# RT1064_CoreBoard.net
KiCad netlist of a schematic drawn in Altium Designer
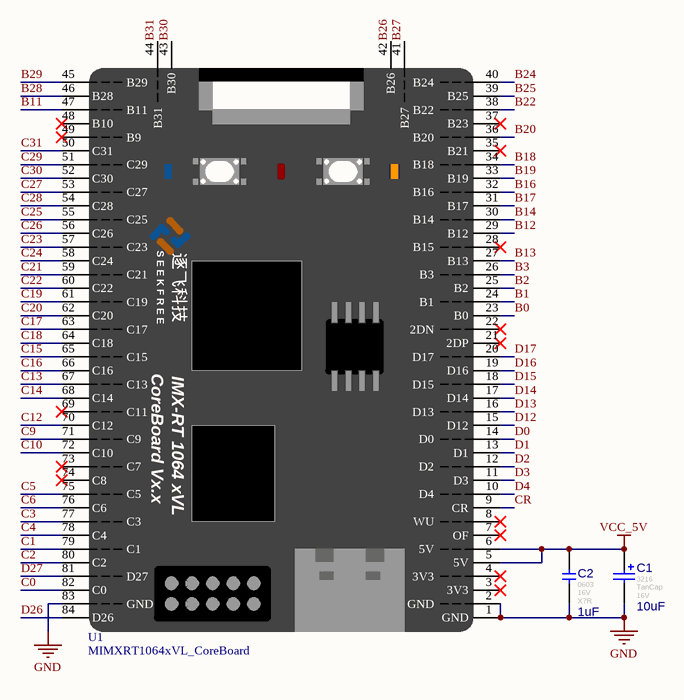
[diagram p0: RT1064_CoreBoard.SchDoc]

(export (version "E")
  (design (tool "Eeschema 10.0.6"))
  (components
    (comp (ref "C1")
      (value "10uF")
      (footprint "3216")
      (description "贴片钽电容 10uF 3216 16V")
      (fields
        (field (name "TYPE") "TanCap")
        (field (name "VOLTAGE") "16V")
        (field (name "Comment") "T-S 10uF 3216 16V")
      )
      (libsource (lib "RT1064 主板 V3.0 器件封装集成库") (part "T-S 10uF 3216 16V"))
    )
    (comp (ref "C2")
      (value "1uF")
      (footprint "0603")
      (description "贴片瓷片电容; MLCC; 0603(1608);")
      (fields
        (field (name "VOLTAGE") "16V")
        (field (name "TYPE") "X7R")
        (field (name "Comment") "1uF 16V X7R")
      )
      (libsource (lib "RT1064 主板 V3.0 器件封装集成库") (part "1uF 0603 16V X7R"))
    )
    (comp (ref "U1")
      (value "MIMXRT1064xVL_CoreBoard")
      (footprint "MIMXRT1064xVL_CoreBoard - 3D")
      (description "逐飞科技i.MX RT1064核心板整体原理，可直接使用")
      (libsource (lib "RT1064 V1.2核心板原理库") (part "MIMXRT1064xVL_CoreBoard"))
    )
  )
  (nets
    (net (code "1") (name "/B0") (class "Default")
      (node (ref "U1") (pin "23") (pinfunction "B0_23") (pintype "passive"))
    )
    (net (code "2") (name "/B1") (class "Default")
      (node (ref "U1") (pin "24") (pinfunction "B1_24") (pintype "passive"))
    )
    (net (code "3") (name "/B2") (class "Default")
      (node (ref "U1") (pin "25") (pinfunction "B2_25") (pintype "passive"))
    )
    (net (code "4") (name "/B3") (class "Default")
      (node (ref "U1") (pin "26") (pinfunction "B3_26") (pintype "passive"))
    )
    (net (code "5") (name "/B11") (class "Default")
      (node (ref "U1") (pin "47") (pinfunction "B11_47") (pintype "passive"))
    )
    (net (code "6") (name "/B12") (class "Default")
      (node (ref "U1") (pin "29") (pinfunction "B12_29") (pintype "passive"))
    )
    (net (code "7") (name "/B13") (class "Default")
      (node (ref "U1") (pin "27") (pinfunction "B13_27") (pintype "passive"))
    )
    (net (code "8") (name "/B14") (class "Default")
      (node (ref "U1") (pin "30") (pinfunction "B14_30") (pintype "passive"))
    )
    (net (code "9") (name "/B16") (class "Default")
      (node (ref "U1") (pin "32") (pinfunction "B16_32") (pintype "passive"))
    )
    (net (code "10") (name "/B17") (class "Default")
      (node (ref "U1") (pin "31") (pinfunction "B17_31") (pintype "passive"))
    )
    (net (code "11") (name "/B18") (class "Default")
      (node (ref "U1") (pin "34") (pinfunction "B18_34") (pintype "passive"))
    )
    (net (code "12") (name "/B19") (class "Default")
      (node (ref "U1") (pin "33") (pinfunction "B19_33") (pintype "passive"))
    )
    (net (code "13") (name "/B20") (class "Default")
      (node (ref "U1") (pin "36") (pinfunction "B20_36") (pintype "passive"))
    )
    (net (code "14") (name "/B22") (class "Default")
      (node (ref "U1") (pin "38") (pinfunction "B22_38") (pintype "passive"))
    )
    (net (code "15") (name "/B24") (class "Default")
      (node (ref "U1") (pin "40") (pinfunction "B24_40") (pintype "passive"))
    )
    (net (code "16") (name "/B25") (class "Default")
      (node (ref "U1") (pin "39") (pinfunction "B25_39") (pintype "passive"))
    )
    (net (code "17") (name "/B26") (class "Default")
      (node (ref "U1") (pin "42") (pinfunction "B26_42") (pintype "passive"))
    )
    (net (code "18") (name "/B27") (class "Default")
      (node (ref "U1") (pin "41") (pinfunction "B27_41") (pintype "passive"))
    )
    (net (code "19") (name "/B28") (class "Default")
      (node (ref "U1") (pin "46") (pinfunction "B28_46") (pintype "passive"))
    )
    (net (code "20") (name "/B29") (class "Default")
      (node (ref "U1") (pin "45") (pinfunction "B29_45") (pintype "passive"))
    )
    (net (code "21") (name "/B30") (class "Default")
      (node (ref "U1") (pin "43") (pinfunction "B30_43") (pintype "passive"))
    )
    (net (code "22") (name "/B31") (class "Default")
      (node (ref "U1") (pin "44") (pinfunction "B31_44") (pintype "passive"))
    )
    (net (code "23") (name "/C0") (class "Default")
      (node (ref "U1") (pin "82") (pinfunction "C0_82") (pintype "passive"))
    )
    (net (code "24") (name "/C1") (class "Default")
      (node (ref "U1") (pin "79") (pinfunction "C1_79") (pintype "passive"))
    )
    (net (code "25") (name "/C2") (class "Default")
      (node (ref "U1") (pin "80") (pinfunction "C2_80") (pintype "passive"))
    )
    (net (code "26") (name "/C3") (class "Default")
      (node (ref "U1") (pin "77") (pinfunction "C3_77") (pintype "passive"))
    )
    (net (code "27") (name "/C4") (class "Default")
      (node (ref "U1") (pin "78") (pinfunction "C4_78") (pintype "passive"))
    )
    (net (code "28") (name "/C5") (class "Default")
      (node (ref "U1") (pin "75") (pinfunction "C5_75") (pintype "passive"))
    )
    (net (code "29") (name "/C6") (class "Default")
      (node (ref "U1") (pin "76") (pinfunction "C6_76") (pintype "passive"))
    )
    (net (code "30") (name "/C9") (class "Default")
      (node (ref "U1") (pin "71") (pinfunction "C9_71") (pintype "passive"))
    )
    (net (code "31") (name "/C10") (class "Default")
      (node (ref "U1") (pin "72") (pinfunction "C10_72") (pintype "passive"))
    )
    (net (code "32") (name "/C12") (class "Default")
      (node (ref "U1") (pin "70") (pinfunction "C12_70") (pintype "passive"))
    )
    (net (code "33") (name "/C13") (class "Default")
      (node (ref "U1") (pin "67") (pinfunction "C13_67") (pintype "passive"))
    )
    (net (code "34") (name "/C14") (class "Default")
      (node (ref "U1") (pin "68") (pinfunction "C14_68") (pintype "passive"))
    )
    (net (code "35") (name "/C15") (class "Default")
      (node (ref "U1") (pin "65") (pinfunction "C15_65") (pintype "passive"))
    )
    (net (code "36") (name "/C16") (class "Default")
      (node (ref "U1") (pin "66") (pinfunction "C16_66") (pintype "passive"))
    )
    (net (code "37") (name "/C17") (class "Default")
      (node (ref "U1") (pin "63") (pinfunction "C17_63") (pintype "passive"))
    )
    (net (code "38") (name "/C18") (class "Default")
      (node (ref "U1") (pin "64") (pinfunction "C18_64") (pintype "passive"))
    )
    (net (code "39") (name "/C19") (class "Default")
      (node (ref "U1") (pin "61") (pinfunction "C19_61") (pintype "passive"))
    )
    (net (code "40") (name "/C20") (class "Default")
      (node (ref "U1") (pin "62") (pinfunction "C20_62") (pintype "passive"))
    )
    (net (code "41") (name "/C21") (class "Default")
      (node (ref "U1") (pin "59") (pinfunction "C21_59") (pintype "passive"))
    )
    (net (code "42") (name "/C22") (class "Default")
      (node (ref "U1") (pin "60") (pinfunction "C22_60") (pintype "passive"))
    )
    (net (code "43") (name "/C23") (class "Default")
      (node (ref "U1") (pin "57") (pinfunction "C23_57") (pintype "passive"))
    )
    (net (code "44") (name "/C24") (class "Default")
      (node (ref "U1") (pin "58") (pinfunction "C24_58") (pintype "passive"))
    )
    (net (code "45") (name "/C25") (class "Default")
      (node (ref "U1") (pin "55") (pinfunction "C25_55") (pintype "passive"))
    )
    (net (code "46") (name "/C26") (class "Default")
      (node (ref "U1") (pin "56") (pinfunction "C26_56") (pintype "passive"))
    )
    (net (code "47") (name "/C27") (class "Default")
      (node (ref "U1") (pin "53") (pinfunction "C27_53") (pintype "passive"))
    )
    (net (code "48") (name "/C28") (class "Default")
      (node (ref "U1") (pin "54") (pinfunction "C28_54") (pintype "passive"))
    )
    (net (code "49") (name "/C29") (class "Default")
      (node (ref "U1") (pin "51") (pinfunction "C29_51") (pintype "passive"))
    )
    (net (code "50") (name "/C30") (class "Default")
      (node (ref "U1") (pin "52") (pinfunction "C30_52") (pintype "passive"))
    )
    (net (code "51") (name "/C31") (class "Default")
      (node (ref "U1") (pin "50") (pinfunction "C31_50") (pintype "passive"))
    )
    (net (code "52") (name "/CR") (class "Default")
      (node (ref "U1") (pin "9") (pinfunction "CR_9") (pintype "passive"))
    )
    (net (code "53") (name "/D0") (class "Default")
      (node (ref "U1") (pin "14") (pinfunction "D0_14") (pintype "passive"))
    )
    (net (code "54") (name "/D1") (class "Default")
      (node (ref "U1") (pin "13") (pinfunction "D1_13") (pintype "passive"))
    )
    (net (code "55") (name "/D2") (class "Default")
      (node (ref "U1") (pin "12") (pinfunction "D2_12") (pintype "passive"))
    )
    (net (code "56") (name "/D3") (class "Default")
      (node (ref "U1") (pin "11") (pinfunction "D3_11") (pintype "passive"))
    )
    (net (code "57") (name "/D4") (class "Default")
      (node (ref "U1") (pin "10") (pinfunction "D4_10") (pintype "passive"))
    )
    (net (code "58") (name "/D12") (class "Default")
      (node (ref "U1") (pin "15") (pinfunction "D12_15") (pintype "passive"))
    )
    (net (code "59") (name "/D13") (class "Default")
      (node (ref "U1") (pin "16") (pinfunction "D13_16") (pintype "passive"))
    )
    (net (code "60") (name "/D14") (class "Default")
      (node (ref "U1") (pin "17") (pinfunction "D14_17") (pintype "passive"))
    )
    (net (code "61") (name "/D15") (class "Default")
      (node (ref "U1") (pin "18") (pinfunction "D15_18") (pintype "passive"))
    )
    (net (code "62") (name "/D16") (class "Default")
      (node (ref "U1") (pin "19") (pinfunction "D16_19") (pintype "passive"))
    )
    (net (code "63") (name "/D17") (class "Default")
      (node (ref "U1") (pin "20") (pinfunction "D17_20") (pintype "passive"))
    )
    (net (code "64") (name "/D26") (class "Default")
      (node (ref "U1") (pin "84") (pinfunction "D26_84") (pintype "passive"))
    )
    (net (code "65") (name "/D27") (class "Default")
      (node (ref "U1") (pin "81") (pinfunction "D27_81") (pintype "passive"))
    )
    (net (code "66") (name "GND") (class "Default")
      (node (ref "C1") (pin "2") (pinfunction "2_2") (pintype "passive"))
      (node (ref "C2") (pin "1") (pinfunction "1_1") (pintype "passive"))
      (node (ref "U1") (pin "1") (pinfunction "GND_1") (pintype "passive"))
      (node (ref "U1") (pin "2") (pinfunction "GND_2") (pintype "passive"))
      (node (ref "U1") (pin "83") (pinfunction "GND_83") (pintype "passive"))
    )
    (net (code "67") (name "VCC_5V") (class "Default")
      (node (ref "C1") (pin "1") (pinfunction "1_1") (pintype "passive"))
      (node (ref "C2") (pin "2") (pinfunction "2_2") (pintype "passive"))
      (node (ref "U1") (pin "5") (pinfunction "5V_5") (pintype "passive"))
      (node (ref "U1") (pin "6") (pinfunction "5V_6") (pintype "passive"))
    )
    (net (code "68") (name "unconnected-(U1-2DN-Pad22)") (class "Default")
      (node (ref "U1") (pin "22") (pinfunction "2DN_22") (pintype "passive+no_connect"))
    )
    (net (code "69") (name "unconnected-(U1-2DP-Pad21)") (class "Default")
      (node (ref "U1") (pin "21") (pinfunction "2DP_21") (pintype "passive+no_connect"))
    )
    (net (code "70") (name "unconnected-(U1-3V3-Pad3)") (class "Default")
      (node (ref "U1") (pin "3") (pinfunction "3V3_3") (pintype "passive+no_connect"))
    )
    (net (code "71") (name "unconnected-(U1-3V3-Pad4)") (class "Default")
      (node (ref "U1") (pin "4") (pinfunction "3V3_4") (pintype "passive+no_connect"))
    )
    (net (code "72") (name "unconnected-(U1-B9-Pad49)") (class "Default")
      (node (ref "U1") (pin "49") (pinfunction "B9_49") (pintype "passive+no_connect"))
    )
    (net (code "73") (name "unconnected-(U1-B10-Pad48)") (class "Default")
      (node (ref "U1") (pin "48") (pinfunction "B10_48") (pintype "passive+no_connect"))
    )
    (net (code "74") (name "unconnected-(U1-B15-Pad28)") (class "Default")
      (node (ref "U1") (pin "28") (pinfunction "B15_28") (pintype "passive+no_connect"))
    )
    (net (code "75") (name "unconnected-(U1-B21-Pad35)") (class "Default")
      (node (ref "U1") (pin "35") (pinfunction "B21_35") (pintype "passive+no_connect"))
    )
    (net (code "76") (name "unconnected-(U1-B23-Pad37)") (class "Default")
      (node (ref "U1") (pin "37") (pinfunction "B23_37") (pintype "passive+no_connect"))
    )
    (net (code "77") (name "unconnected-(U1-C7-Pad73)") (class "Default")
      (node (ref "U1") (pin "73") (pinfunction "C7_73") (pintype "passive+no_connect"))
    )
    (net (code "78") (name "unconnected-(U1-C8-Pad74)") (class "Default")
      (node (ref "U1") (pin "74") (pinfunction "C8_74") (pintype "passive+no_connect"))
    )
    (net (code "79") (name "unconnected-(U1-C11-Pad69)") (class "Default")
      (node (ref "U1") (pin "69") (pinfunction "C11_69") (pintype "passive+no_connect"))
    )
    (net (code "80") (name "unconnected-(U1-OF-Pad7)") (class "Default")
      (node (ref "U1") (pin "7") (pinfunction "OF_7") (pintype "passive+no_connect"))
    )
    (net (code "81") (name "unconnected-(U1-WU-Pad8)") (class "Default")
      (node (ref "U1") (pin "8") (pinfunction "WU_8") (pintype "passive+no_connect"))
    )
  )
)
